# schematic-50m-esp.net
KiCad netlist of a schematic drawn in Altium Designer
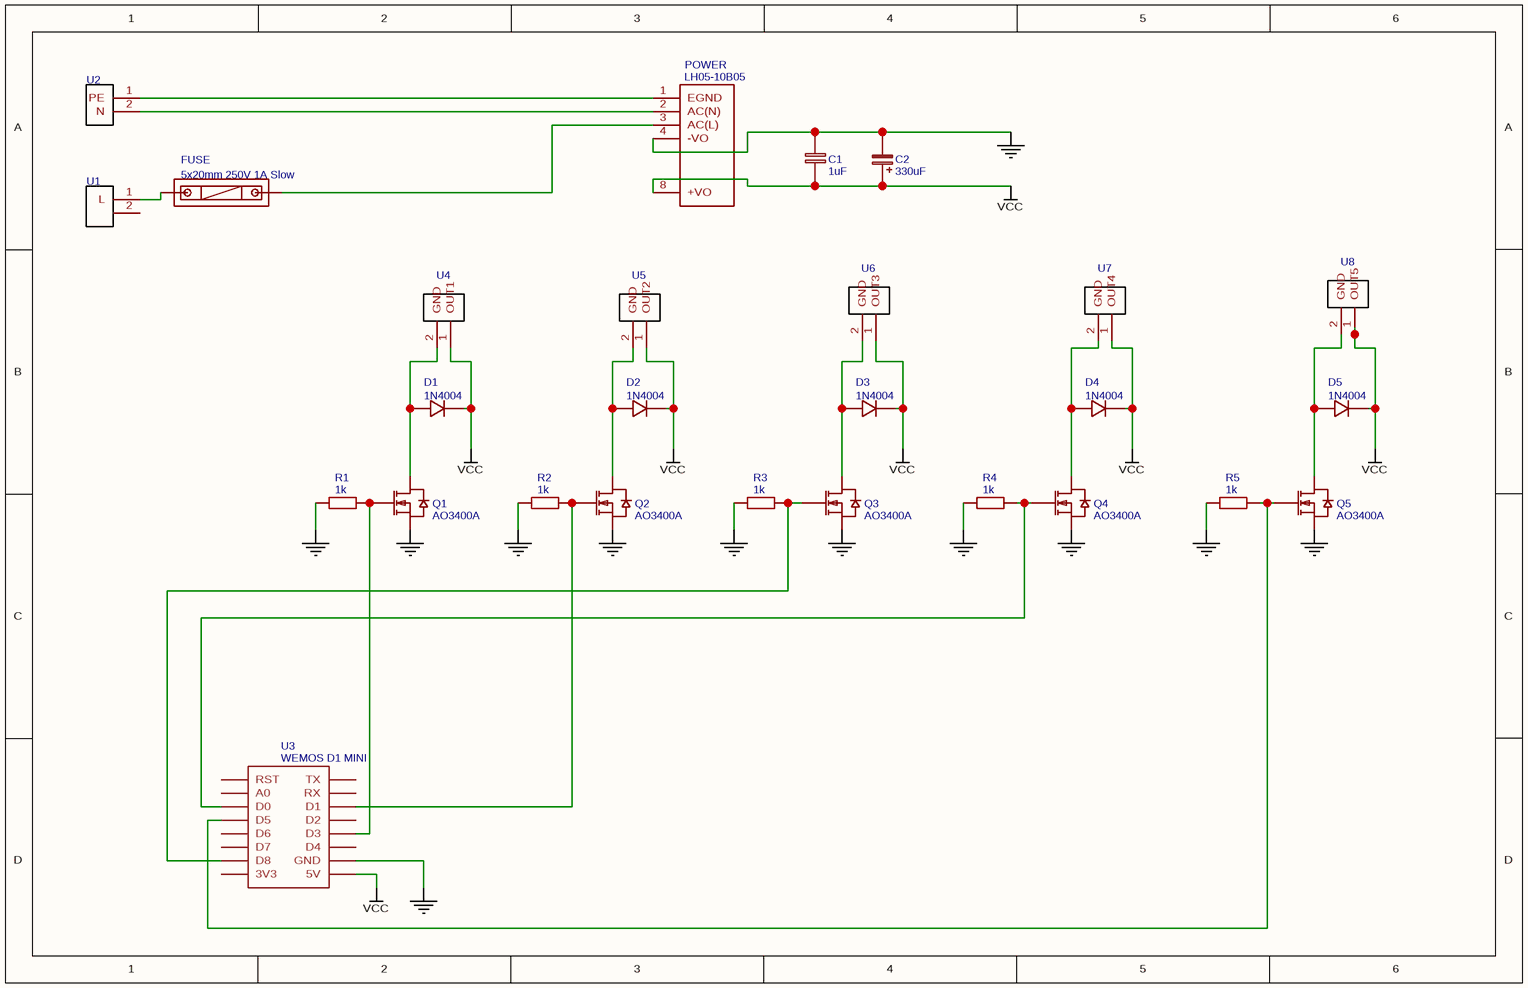
[diagram p0: schematic-50m-esp.schdoc]

(export (version "E")
  (design (tool "Eeschema 10.0.6"))
  (components
    (comp (ref "C1")
      (value "1uF")
      (fields (field (name "BOM_MANUFACTURER PART") "?"))
      (libsource (lib "altium-import") (part "root_0_1uF_"))
    )
    (comp (ref "C2")
      (value "330uF")
      (fields (field (name "BOM_MANUFACTURER PART") "?") (field (name "CONTRIBUTOR") "EasyEDA"))
      (libsource (lib "altium-import") (part "root_2_330uF_"))
    )
    (comp (ref "D1")
      (value "1N4004")
      (fields (field (name "BOM_SUPPLIER PART") "C3058") (field (name "CONTRIBUTOR") "LCSC"))
      (libsource (lib "altium-import") (part "root_0_1N4004_"))
    )
    (comp (ref "D2")
      (value "1N4004")
      (fields (field (name "BOM_SUPPLIER PART") "C3058") (field (name "CONTRIBUTOR") "LCSC"))
      (libsource (lib "altium-import") (part "root_0_1N4004_"))
    )
    (comp (ref "D3")
      (value "1N4004")
      (fields (field (name "BOM_SUPPLIER PART") "C3058") (field (name "CONTRIBUTOR") "LCSC"))
      (libsource (lib "altium-import") (part "root_0_1N4004_"))
    )
    (comp (ref "D4")
      (value "1N4004")
      (fields (field (name "BOM_SUPPLIER PART") "C3058") (field (name "CONTRIBUTOR") "LCSC"))
      (libsource (lib "altium-import") (part "root_0_1N4004_"))
    )
    (comp (ref "D5")
      (value "1N4004")
      (fields (field (name "BOM_SUPPLIER PART") "C3058") (field (name "CONTRIBUTOR") "LCSC"))
      (libsource (lib "altium-import") (part "root_0_1N4004_"))
    )
    (comp (ref "FUSE")
      (value "5x20mm 250V 1A Slow")
      (fields
        (field (name "BOM_MANUFACTURER PART") "Fuse transparent seat")
        (field (name "BOM_SUPPLIER PART") "C58066")
      )
      (libsource (lib "altium-import") (part "root_0_5x20mm 250V 1A Slow_"))
    )
    (comp (ref "POWER")
      (value "LH05-10B05")
      (fields (field (name "BOM_SUPPLIER PART") "C91816"))
      (libsource (lib "altium-import") (part "root_0_LH05-10B05_"))
    )
    (comp (ref "Q1")
      (value "AO3400A")
      (fields (field (name "BOM_SUPPLIER PART") "C20917") (field (name "CONTRIBUTOR") "LCSC"))
      (libsource (lib "altium-import") (part "root_0_AO3400A_"))
    )
    (comp (ref "Q2")
      (value "AO3400A")
      (fields (field (name "BOM_SUPPLIER PART") "C20917") (field (name "CONTRIBUTOR") "LCSC"))
      (libsource (lib "altium-import") (part "root_0_AO3400A_"))
    )
    (comp (ref "Q3")
      (value "AO3400A")
      (fields (field (name "BOM_SUPPLIER PART") "C20917") (field (name "CONTRIBUTOR") "LCSC"))
      (libsource (lib "altium-import") (part "root_0_AO3400A_"))
    )
    (comp (ref "Q4")
      (value "AO3400A")
      (fields (field (name "BOM_SUPPLIER PART") "C20917") (field (name "CONTRIBUTOR") "LCSC"))
      (libsource (lib "altium-import") (part "root_0_AO3400A_"))
    )
    (comp (ref "Q5")
      (value "AO3400A")
      (fields (field (name "BOM_SUPPLIER PART") "C20917") (field (name "CONTRIBUTOR") "LCSC"))
      (libsource (lib "altium-import") (part "root_0_AO3400A_"))
    )
    (comp (ref "R1")
      (value "1k")
      (fields (field (name "BOM_MANUFACTURER PART") "?"))
      (libsource (lib "altium-import") (part "root_0_1k_"))
    )
    (comp (ref "R2")
      (value "1k")
      (fields (field (name "BOM_MANUFACTURER PART") "?"))
      (libsource (lib "altium-import") (part "root_0_1k_"))
    )
    (comp (ref "R3")
      (value "1k")
      (fields (field (name "BOM_MANUFACTURER PART") "?"))
      (libsource (lib "altium-import") (part "root_0_1k_"))
    )
    (comp (ref "R4")
      (value "1k")
      (fields (field (name "BOM_MANUFACTURER PART") "?"))
      (libsource (lib "altium-import") (part "root_0_1k_"))
    )
    (comp (ref "R5")
      (value "1k")
      (fields (field (name "BOM_MANUFACTURER PART") "?"))
      (libsource (lib "altium-import") (part "root_0_1k_"))
    )
    (comp (ref "U1")
      (value "1x2 5mm Screw Terminals")
      (fields (field (name "CONTRIBUTOR") "IDVert3X"))
      (libsource (lib "altium-import") (part "root_0_1x2 5mm Screw Terminals_"))
    )
    (comp (ref "U2")
      (value "1x2 5mm Screw Terminals")
      (fields (field (name "CONTRIBUTOR") "IDVert3X"))
      (libsource (lib "altium-import") (part "root_0_1x2 5mm Screw Terminals_"))
    )
    (comp (ref "U3")
      (value "WEMOS D1 MINI")
      (fields (field (name "BOM_MANUFACTURER PART") "?"))
      (libsource (lib "altium-import") (part "root_0_WEMOS D1 MINI_"))
    )
    (comp (ref "U4")
      (value "1x2 5mm Screw Terminals")
      (fields (field (name "CONTRIBUTOR") "IDVert3X"))
      (libsource (lib "altium-import") (part "root_3_1x2 5mm Screw Terminals_"))
    )
    (comp (ref "U5")
      (value "1x2 5mm Screw Terminals")
      (fields (field (name "CONTRIBUTOR") "IDVert3X"))
      (libsource (lib "altium-import") (part "root_3_1x2 5mm Screw Terminals_"))
    )
    (comp (ref "U6")
      (value "1x2 5mm Screw Terminals")
      (fields (field (name "CONTRIBUTOR") "IDVert3X"))
      (libsource (lib "altium-import") (part "root_3_1x2 5mm Screw Terminals_"))
    )
    (comp (ref "U7")
      (value "1x2 5mm Screw Terminals")
      (fields (field (name "CONTRIBUTOR") "IDVert3X"))
      (libsource (lib "altium-import") (part "root_3_1x2 5mm Screw Terminals_"))
    )
    (comp (ref "U8")
      (value "1x2 5mm Screw Terminals")
      (fields (field (name "CONTRIBUTOR") "IDVert3X"))
      (libsource (lib "altium-import") (part "root_3_1x2 5mm Screw Terminals_"))
    )
  )
  (nets
    (net (code "1") (name "GND") (class "Default")
      (node (ref "C1") (pin "1") (pinfunction "1_1") (pintype "passive"))
      (node (ref "C2") (pin "2") (pinfunction "2_2") (pintype "passive"))
      (node (ref "POWER") (pin "4") (pinfunction "-VO_4") (pintype "passive"))
      (node (ref "Q1") (pin "2") (pinfunction "S_2") (pintype "passive"))
      (node (ref "Q2") (pin "2") (pinfunction "S_2") (pintype "passive"))
      (node (ref "Q3") (pin "2") (pinfunction "S_2") (pintype "passive"))
      (node (ref "Q4") (pin "2") (pinfunction "S_2") (pintype "passive"))
      (node (ref "Q5") (pin "2") (pinfunction "S_2") (pintype "passive"))
      (node (ref "R1") (pin "1") (pinfunction "1_1") (pintype "passive"))
      (node (ref "R2") (pin "1") (pinfunction "1_1") (pintype "passive"))
      (node (ref "R3") (pin "1") (pinfunction "1_1") (pintype "passive"))
      (node (ref "R4") (pin "1") (pinfunction "1_1") (pintype "passive"))
      (node (ref "R5") (pin "1") (pinfunction "1_1") (pintype "passive"))
      (node (ref "U3") (pin "GND") (pinfunction "GND_GND") (pintype "passive"))
    )
    (net (code "2") (name "Net-(D1-A)") (class "Default")
      (node (ref "D1") (pin "1") (pinfunction "A_1") (pintype "passive"))
      (node (ref "Q1") (pin "3") (pinfunction "D_3") (pintype "passive"))
      (node (ref "U4") (pin "2") (pinfunction "GND_2") (pintype "passive"))
    )
    (net (code "3") (name "Net-(D2-A)") (class "Default")
      (node (ref "D2") (pin "1") (pinfunction "A_1") (pintype "passive"))
      (node (ref "Q2") (pin "3") (pinfunction "D_3") (pintype "passive"))
      (node (ref "U5") (pin "2") (pinfunction "GND_2") (pintype "passive"))
    )
    (net (code "4") (name "Net-(D3-A)") (class "Default")
      (node (ref "D3") (pin "1") (pinfunction "A_1") (pintype "passive"))
      (node (ref "Q3") (pin "3") (pinfunction "D_3") (pintype "passive"))
      (node (ref "U6") (pin "2") (pinfunction "GND_2") (pintype "passive"))
    )
    (net (code "5") (name "Net-(D4-A)") (class "Default")
      (node (ref "D4") (pin "1") (pinfunction "A_1") (pintype "passive"))
      (node (ref "Q4") (pin "3") (pinfunction "D_3") (pintype "passive"))
      (node (ref "U7") (pin "2") (pinfunction "GND_2") (pintype "passive"))
    )
    (net (code "6") (name "Net-(D5-A)") (class "Default")
      (node (ref "D5") (pin "1") (pinfunction "A_1") (pintype "passive"))
      (node (ref "Q5") (pin "3") (pinfunction "D_3") (pintype "passive"))
      (node (ref "U8") (pin "2") (pinfunction "GND_2") (pintype "passive"))
    )
    (net (code "7") (name "Net-(POWER-AC(L))") (class "Default")
      (node (ref "FUSE") (pin "2") (pinfunction "2_2") (pintype "passive"))
      (node (ref "POWER") (pin "3") (pinfunction "AC(L)_3") (pintype "passive"))
    )
    (net (code "8") (name "Net-(POWER-AC(N))") (class "Default")
      (node (ref "POWER") (pin "2") (pinfunction "AC(N)_2") (pintype "passive"))
      (node (ref "U2") (pin "2") (pinfunction "N_2") (pintype "passive"))
    )
    (net (code "9") (name "Net-(POWER-EGND)") (class "Default")
      (node (ref "POWER") (pin "1") (pinfunction "EGND_1") (pintype "passive"))
      (node (ref "U2") (pin "1") (pinfunction "L_1") (pintype "passive"))
    )
    (net (code "10") (name "Net-(Q1-G)") (class "Default")
      (node (ref "Q1") (pin "1") (pinfunction "G_1") (pintype "passive"))
      (node (ref "R1") (pin "2") (pinfunction "2_2") (pintype "passive"))
      (node (ref "U3") (pin "D3") (pinfunction "D3_D3") (pintype "passive"))
    )
    (net (code "11") (name "Net-(Q2-G)") (class "Default")
      (node (ref "Q2") (pin "1") (pinfunction "G_1") (pintype "passive"))
      (node (ref "R2") (pin "2") (pinfunction "2_2") (pintype "passive"))
      (node (ref "U3") (pin "D1") (pinfunction "D1_D1") (pintype "passive"))
    )
    (net (code "12") (name "Net-(Q3-G)") (class "Default")
      (node (ref "Q3") (pin "1") (pinfunction "G_1") (pintype "passive"))
      (node (ref "R3") (pin "2") (pinfunction "2_2") (pintype "passive"))
      (node (ref "U3") (pin "D8") (pinfunction "D8_D8") (pintype "passive"))
    )
    (net (code "13") (name "Net-(Q4-G)") (class "Default")
      (node (ref "Q4") (pin "1") (pinfunction "G_1") (pintype "passive"))
      (node (ref "R4") (pin "2") (pinfunction "2_2") (pintype "passive"))
      (node (ref "U3") (pin "D0") (pinfunction "D0_D0") (pintype "passive"))
    )
    (net (code "14") (name "Net-(Q5-G)") (class "Default")
      (node (ref "Q5") (pin "1") (pinfunction "G_1") (pintype "passive"))
      (node (ref "R5") (pin "2") (pinfunction "2_2") (pintype "passive"))
      (node (ref "U3") (pin "D5") (pinfunction "D5_D5") (pintype "passive"))
    )
    (net (code "15") (name "Net-(U1-L)") (class "Default")
      (node (ref "FUSE") (pin "1") (pinfunction "1_1") (pintype "passive"))
      (node (ref "U1") (pin "1") (pinfunction "L_1") (pintype "passive"))
    )
    (net (code "16") (name "VCC") (class "Default")
      (node (ref "C1") (pin "2") (pinfunction "2_2") (pintype "passive"))
      (node (ref "C2") (pin "1") (pinfunction "1_1") (pintype "passive"))
      (node (ref "D1") (pin "2") (pinfunction "K_2") (pintype "passive"))
      (node (ref "D2") (pin "2") (pinfunction "K_2") (pintype "passive"))
      (node (ref "D3") (pin "2") (pinfunction "K_2") (pintype "passive"))
      (node (ref "D4") (pin "2") (pinfunction "K_2") (pintype "passive"))
      (node (ref "D5") (pin "2") (pinfunction "K_2") (pintype "passive"))
      (node (ref "POWER") (pin "8") (pinfunction "+VO_8") (pintype "passive"))
      (node (ref "U3") (pin "5V") (pinfunction "5V_5V") (pintype "passive"))
      (node (ref "U4") (pin "1") (pinfunction "OUT1_1") (pintype "passive"))
      (node (ref "U5") (pin "1") (pinfunction "OUT1_1") (pintype "passive"))
      (node (ref "U6") (pin "1") (pinfunction "OUT1_1") (pintype "passive"))
      (node (ref "U7") (pin "1") (pinfunction "OUT1_1") (pintype "passive"))
      (node (ref "U8") (pin "1") (pinfunction "OUT1_1") (pintype "passive"))
    )
    (net (code "17") (name "unconnected-(U1-N-Pad2)") (class "Default")
      (node (ref "U1") (pin "2") (pinfunction "N_2") (pintype "passive"))
    )
    (net (code "18") (name "unconnected-(U3-Pad3V3)") (class "Default")
      (node (ref "U3") (pin "3V3") (pinfunction "3V3_3V3") (pintype "passive"))
    )
    (net (code "19") (name "unconnected-(U3-PadA0)") (class "Default")
      (node (ref "U3") (pin "A0") (pinfunction "A0_A0") (pintype "passive"))
    )
    (net (code "20") (name "unconnected-(U3-PadD2)") (class "Default")
      (node (ref "U3") (pin "D2") (pinfunction "D2_D2") (pintype "passive"))
    )
    (net (code "21") (name "unconnected-(U3-PadD4)") (class "Default")
      (node (ref "U3") (pin "D4") (pinfunction "D4_D4") (pintype "passive"))
    )
    (net (code "22") (name "unconnected-(U3-PadD6)") (class "Default")
      (node (ref "U3") (pin "D6") (pinfunction "D6_D6") (pintype "passive"))
    )
    (net (code "23") (name "unconnected-(U3-PadD7)") (class "Default")
      (node (ref "U3") (pin "D7") (pinfunction "D7_D7") (pintype "passive"))
    )
    (net (code "24") (name "unconnected-(U3-PadRST)") (class "Default")
      (node (ref "U3") (pin "RST") (pinfunction "RST_RST") (pintype "passive"))
    )
    (net (code "25") (name "unconnected-(U3-PadRX)") (class "Default")
      (node (ref "U3") (pin "RX") (pinfunction "RX_RX") (pintype "passive"))
    )
    (net (code "26") (name "unconnected-(U3-PadTX)") (class "Default")
      (node (ref "U3") (pin "TX") (pinfunction "TX_TX") (pintype "passive"))
    )
  )
)
